# design.net
KiCad netlist of a schematic drawn in Altium Designer
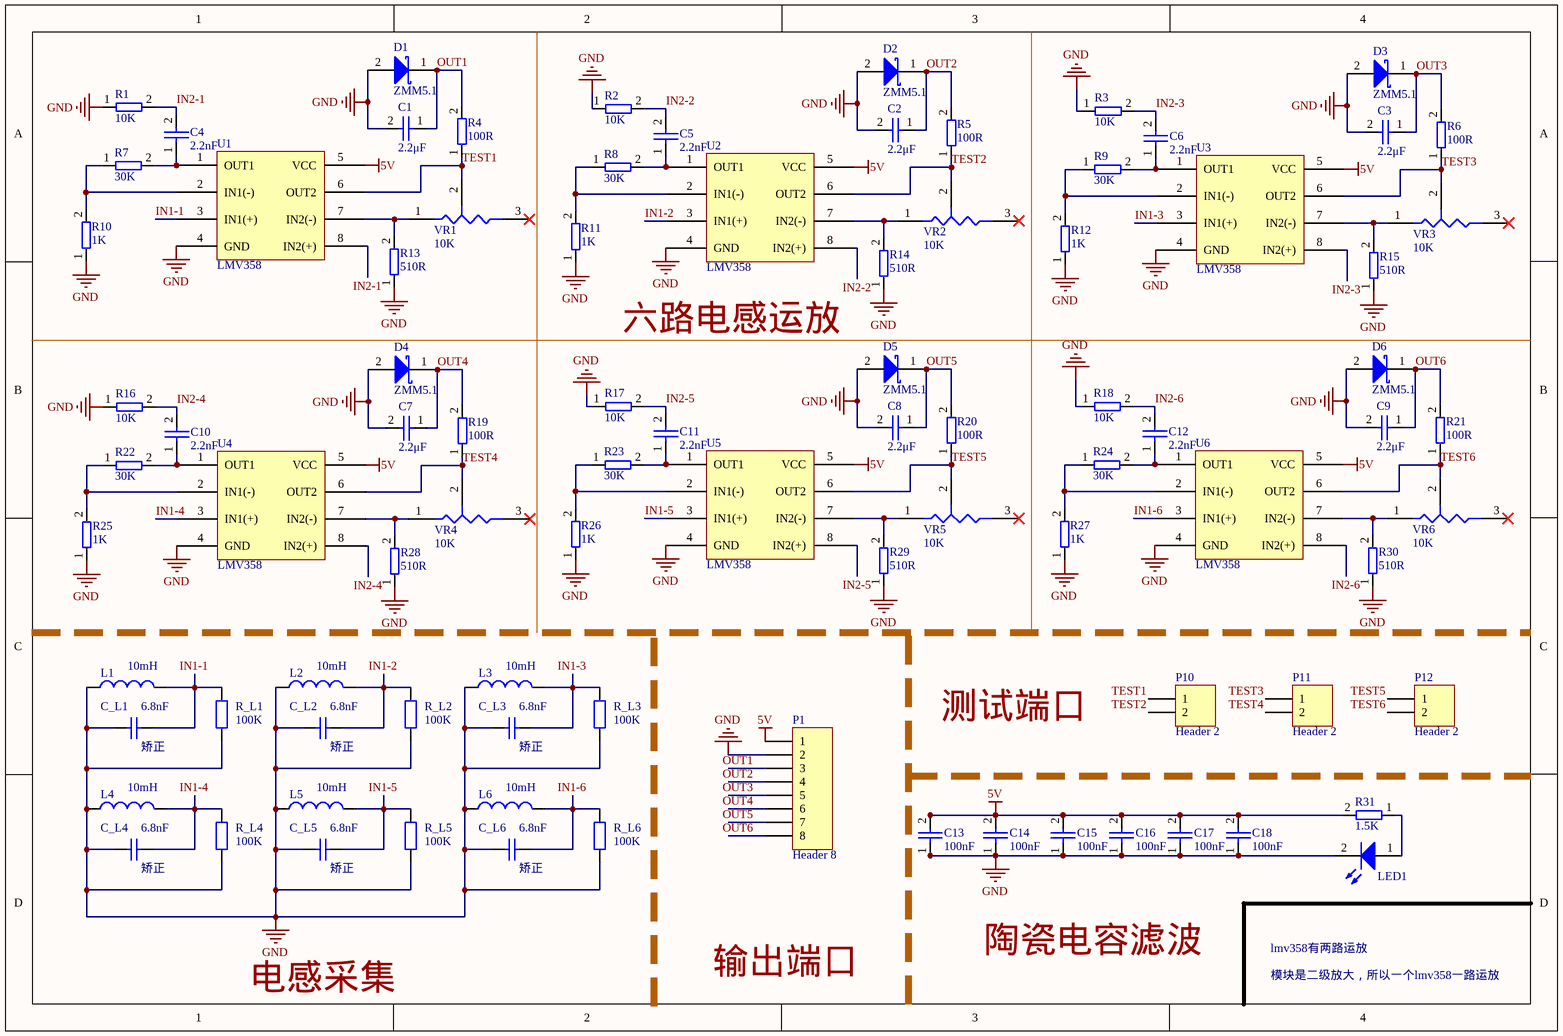
[diagram p0: 电感板原理图.SchDoc]

(export (version "E")
  (design (tool "Eeschema 10.0.6"))
  (components
    (comp (ref "C1") (value "2.2μF") (footprint "C 0603_L") (libsource (lib "燚龘") (part "Cap")))
    (comp (ref "C2") (value "2.2μF") (footprint "C 0603_L") (libsource (lib "燚龘") (part "Cap")))
    (comp (ref "C3") (value "2.2μF") (footprint "C 0603_L") (libsource (lib "燚龘") (part "Cap")))
    (comp (ref "C4") (value "2.2nF") (footprint "0805C") (libsource (lib "燚龘") (part "Cap")))
    (comp (ref "C5") (value "2.2nF") (footprint "0805C") (libsource (lib "燚龘") (part "Cap")))
    (comp (ref "C6") (value "2.2nF") (footprint "0805C") (libsource (lib "燚龘") (part "Cap")))
    (comp (ref "C7") (value "2.2μF") (footprint "C 0603_L") (libsource (lib "燚龘") (part "Cap")))
    (comp (ref "C8") (value "2.2μF") (footprint "C 0603_L") (libsource (lib "燚龘") (part "Cap")))
    (comp (ref "C9") (value "2.2μF") (footprint "C 0603_L") (libsource (lib "燚龘") (part "Cap")))
    (comp (ref "C10") (value "2.2nF") (footprint "0805C") (libsource (lib "燚龘") (part "Cap")))
    (comp (ref "C11") (value "2.2nF") (footprint "0805C") (libsource (lib "燚龘") (part "Cap")))
    (comp (ref "C12") (value "2.2nF") (footprint "0805C") (libsource (lib "燚龘") (part "Cap")))
    (comp (ref "C13")
      (value "100nF")
      (footprint "0805C")
      (description "陶瓷电容")
      (libsource (lib "燚龘") (part "Cap"))
    )
    (comp (ref "C14")
      (value "100nF")
      (footprint "0805C")
      (description "陶瓷电容")
      (libsource (lib "燚龘") (part "Cap"))
    )
    (comp (ref "C15")
      (value "100nF")
      (footprint "0805C")
      (description "陶瓷电容")
      (libsource (lib "燚龘") (part "Cap"))
    )
    (comp (ref "C16")
      (value "100nF")
      (footprint "0805C")
      (description "陶瓷电容")
      (libsource (lib "燚龘") (part "Cap"))
    )
    (comp (ref "C17")
      (value "100nF")
      (footprint "0805C")
      (description "陶瓷电容")
      (libsource (lib "燚龘") (part "Cap"))
    )
    (comp (ref "C18")
      (value "100nF")
      (footprint "0805C")
      (description "陶瓷电容")
      (libsource (lib "燚龘") (part "Cap"))
    )
    (comp (ref "C_L1")
      (value "矫正")
      (footprint "RAD-0.3")
      (description "Capacitor")
      (fields (field (name "ALTIUM_VALUE") "6.8nF") (field (name "PUBLISHER") "Altium Limited"))
      (libsource (lib "Miscellaneous Devices") (part "Cap"))
    )
    (comp (ref "C_L2")
      (value "矫正")
      (footprint "RAD-0.3")
      (description "Capacitor")
      (fields (field (name "ALTIUM_VALUE") "6.8nF") (field (name "PUBLISHER") "Altium Limited"))
      (libsource (lib "Miscellaneous Devices") (part "Cap"))
    )
    (comp (ref "C_L3")
      (value "矫正")
      (footprint "RAD-0.3")
      (description "Capacitor")
      (fields (field (name "ALTIUM_VALUE") "6.8nF") (field (name "PUBLISHER") "Altium Limited"))
      (libsource (lib "Miscellaneous Devices") (part "Cap"))
    )
    (comp (ref "C_L4")
      (value "矫正")
      (footprint "RAD-0.3")
      (description "Capacitor")
      (fields (field (name "ALTIUM_VALUE") "6.8nF") (field (name "PUBLISHER") "Altium Limited"))
      (libsource (lib "Miscellaneous Devices") (part "Cap"))
    )
    (comp (ref "C_L5")
      (value "矫正")
      (footprint "RAD-0.3")
      (description "Capacitor")
      (fields (field (name "ALTIUM_VALUE") "6.8nF") (field (name "PUBLISHER") "Altium Limited"))
      (libsource (lib "Miscellaneous Devices") (part "Cap"))
    )
    (comp (ref "C_L6")
      (value "矫正")
      (footprint "RAD-0.3")
      (description "Capacitor")
      (fields (field (name "ALTIUM_VALUE") "6.8nF") (field (name "PUBLISHER") "Altium Limited"))
      (libsource (lib "Miscellaneous Devices") (part "Cap"))
    )
    (comp (ref "D1")
      (value "ZMM5.1")
      (footprint "1206C")
      (description "Schottky Rectifier")
      (fields (field (name "PUBLISHER") "Altium Limited"))
      (libsource (lib "Miscellaneous Devices") (part "Diode 10TQ040"))
    )
    (comp (ref "D2")
      (value "ZMM5.1")
      (footprint "1206C")
      (description "Schottky Rectifier")
      (fields (field (name "PUBLISHER") "Altium Limited"))
      (libsource (lib "Miscellaneous Devices") (part "Diode 10TQ040"))
    )
    (comp (ref "D3")
      (value "ZMM5.1")
      (footprint "1206C")
      (description "Schottky Rectifier")
      (fields (field (name "PUBLISHER") "Altium Limited"))
      (libsource (lib "Miscellaneous Devices") (part "Diode 10TQ040"))
    )
    (comp (ref "D4")
      (value "ZMM5.1")
      (footprint "1206C")
      (description "Schottky Rectifier")
      (fields (field (name "PUBLISHER") "Altium Limited"))
      (libsource (lib "Miscellaneous Devices") (part "Diode 10TQ040"))
    )
    (comp (ref "D5")
      (value "ZMM5.1")
      (footprint "1206C")
      (description "Schottky Rectifier")
      (fields (field (name "PUBLISHER") "Altium Limited"))
      (libsource (lib "Miscellaneous Devices") (part "Diode 10TQ040"))
    )
    (comp (ref "D6")
      (value "ZMM5.1")
      (footprint "1206C")
      (description "Schottky Rectifier")
      (fields (field (name "PUBLISHER") "Altium Limited"))
      (libsource (lib "Miscellaneous Devices") (part "Diode 10TQ040"))
    )
    (comp (ref "L1")
      (value "10mH")
      (footprint "HDR1X2")
      (description "Inductor")
      (fields (field (name "PUBLISHER") "Altium Limited"))
      (libsource (lib "Miscellaneous Devices") (part "Inductor"))
    )
    (comp (ref "L2")
      (value "10mH")
      (footprint "HDR1X2")
      (description "Inductor")
      (fields (field (name "PUBLISHER") "Altium Limited"))
      (libsource (lib "Miscellaneous Devices") (part "Inductor"))
    )
    (comp (ref "L3")
      (value "10mH")
      (footprint "HDR1X2")
      (description "Inductor")
      (fields (field (name "PUBLISHER") "Altium Limited"))
      (libsource (lib "Miscellaneous Devices") (part "Inductor"))
    )
    (comp (ref "L4")
      (value "10mH")
      (footprint "HDR1X2")
      (description "Inductor")
      (fields (field (name "PUBLISHER") "Altium Limited"))
      (libsource (lib "Miscellaneous Devices") (part "Inductor"))
    )
    (comp (ref "L5")
      (value "10mH")
      (footprint "HDR1X2")
      (description "Inductor")
      (fields (field (name "PUBLISHER") "Altium Limited"))
      (libsource (lib "Miscellaneous Devices") (part "Inductor"))
    )
    (comp (ref "L6")
      (value "10mH")
      (footprint "HDR1X2")
      (description "Inductor")
      (fields (field (name "PUBLISHER") "Altium Limited"))
      (libsource (lib "Miscellaneous Devices") (part "Inductor"))
    )
    (comp (ref "LED1")
      (value "LED")
      (footprint "LED0805R")
      (description "Typical BLUE SiC LED")
      (fields (field (name "PUBLISHER") "Altium Limited"))
      (libsource (lib "智能车修改版") (part "LED3"))
    )
    (comp (ref "P1")
      (value "Header 8")
      (footprint "HDR1X8")
      (description "Header, 8-Pin")
      (fields (field (name "PUBLISHER") "Altium Limited"))
      (libsource (lib "红旗_SchLib_V1.0") (part "Header 8"))
    )
    (comp (ref "P10")
      (value "Header 2")
      (footprint "HDR1X2")
      (description "Header, 2-Pin")
      (fields (field (name "PUBLISHER") "Altium Limited"))
      (libsource (lib "Miscellaneous Connectors") (part "Header 2"))
    )
    (comp (ref "P11")
      (value "Header 2")
      (footprint "HDR1X2")
      (description "Header, 2-Pin")
      (fields (field (name "PUBLISHER") "Altium Limited"))
      (libsource (lib "Miscellaneous Connectors") (part "Header 2"))
    )
    (comp (ref "P12")
      (value "Header 2")
      (footprint "HDR1X2")
      (description "Header, 2-Pin")
      (fields (field (name "PUBLISHER") "Altium Limited"))
      (libsource (lib "Miscellaneous Connectors") (part "Header 2"))
    )
    (comp (ref "R1") (value "10K") (footprint "0805-1R") (libsource (lib "燚龘主控") (part "0805R")))
    (comp (ref "R2") (value "10K") (footprint "0805-1R") (libsource (lib "燚龘主控") (part "0805R")))
    (comp (ref "R3") (value "10K") (footprint "0805-1R") (libsource (lib "燚龘主控") (part "0805R")))
    (comp (ref "R4") (value "100R") (footprint "0805-0R") (libsource (lib "燚龘主控") (part "0805R")))
    (comp (ref "R5") (value "100R") (footprint "0805-0R") (libsource (lib "燚龘主控") (part "0805R")))
    (comp (ref "R6") (value "100R") (footprint "0805-0R") (libsource (lib "燚龘主控") (part "0805R")))
    (comp (ref "R7") (value "30K") (footprint "0805-1R") (libsource (lib "燚龘主控") (part "0805R")))
    (comp (ref "R8") (value "30K") (footprint "0805-1R") (libsource (lib "燚龘主控") (part "0805R")))
    (comp (ref "R9") (value "30K") (footprint "0805-1R") (libsource (lib "燚龘主控") (part "0805R")))
    (comp (ref "R10") (value "1K") (footprint "0805-1R") (libsource (lib "燚龘主控") (part "0805R")))
    (comp (ref "R11") (value "1K") (footprint "0805-1R") (libsource (lib "燚龘主控") (part "0805R")))
    (comp (ref "R12") (value "1K") (footprint "0805-1R") (libsource (lib "燚龘主控") (part "0805R")))
    (comp (ref "R13") (value "510R") (footprint "0805-0R") (libsource (lib "燚龘主控") (part "0805R")))
    (comp (ref "R14") (value "510R") (footprint "0805-0R") (libsource (lib "燚龘主控") (part "0805R")))
    (comp (ref "R15") (value "510R") (footprint "0805-0R") (libsource (lib "燚龘主控") (part "0805R")))
    (comp (ref "R16") (value "10K") (footprint "0805-1R") (libsource (lib "燚龘主控") (part "0805R")))
    (comp (ref "R17") (value "10K") (footprint "0805-1R") (libsource (lib "燚龘主控") (part "0805R")))
    (comp (ref "R18") (value "10K") (footprint "0805-1R") (libsource (lib "燚龘主控") (part "0805R")))
    (comp (ref "R19") (value "100R") (footprint "0805-0R") (libsource (lib "燚龘主控") (part "0805R")))
    (comp (ref "R20") (value "100R") (footprint "0805-0R") (libsource (lib "燚龘主控") (part "0805R")))
    (comp (ref "R21") (value "100R") (footprint "0805-0R") (libsource (lib "燚龘主控") (part "0805R")))
    (comp (ref "R22") (value "30K") (footprint "0805-1R") (libsource (lib "燚龘主控") (part "0805R")))
    (comp (ref "R23") (value "30K") (footprint "0805-1R") (libsource (lib "燚龘主控") (part "0805R")))
    (comp (ref "R24") (value "30K") (footprint "0805-1R") (libsource (lib "燚龘主控") (part "0805R")))
    (comp (ref "R25") (value "1K") (footprint "0805-1R") (libsource (lib "燚龘主控") (part "0805R")))
    (comp (ref "R26") (value "1K") (footprint "0805-1R") (libsource (lib "燚龘主控") (part "0805R")))
    (comp (ref "R27") (value "1K") (footprint "0805-1R") (libsource (lib "燚龘主控") (part "0805R")))
    (comp (ref "R28") (value "510R") (footprint "0805-0R") (libsource (lib "燚龘主控") (part "0805R")))
    (comp (ref "R29") (value "510R") (footprint "0805-0R") (libsource (lib "燚龘主控") (part "0805R")))
    (comp (ref "R30") (value "510R") (footprint "0805-0R") (libsource (lib "燚龘主控") (part "0805R")))
    (comp (ref "R31") (value "1.5K") (footprint "0805-1R") (libsource (lib "燚龘主控") (part "0805R")))
    (comp (ref "R_L1")
      (value "100K")
      (footprint "0805-1R")
      (description "Resistor")
      (fields (field (name "Comment") "Res2") (field (name "PUBLISHER") "Altium Limited"))
      (libsource (lib "Miscellaneous Devices") (part "Res2"))
    )
    (comp (ref "R_L2")
      (value "100K")
      (footprint "0805-1R")
      (description "Resistor")
      (fields (field (name "Comment") "Res2") (field (name "PUBLISHER") "Altium Limited"))
      (libsource (lib "Miscellaneous Devices") (part "Res2"))
    )
    (comp (ref "R_L3")
      (value "100K")
      (footprint "0805-1R")
      (description "Resistor")
      (fields (field (name "Comment") "Res2") (field (name "PUBLISHER") "Altium Limited"))
      (libsource (lib "Miscellaneous Devices") (part "Res2"))
    )
    (comp (ref "R_L4")
      (value "100K")
      (footprint "0805-1R")
      (description "Resistor")
      (fields (field (name "Comment") "Res2") (field (name "PUBLISHER") "Altium Limited"))
      (libsource (lib "Miscellaneous Devices") (part "Res2"))
    )
    (comp (ref "R_L5")
      (value "100K")
      (footprint "0805-1R")
      (description "Resistor")
      (fields (field (name "Comment") "Res2") (field (name "PUBLISHER") "Altium Limited"))
      (libsource (lib "Miscellaneous Devices") (part "Res2"))
    )
    (comp (ref "R_L6")
      (value "100K")
      (footprint "0805-1R")
      (description "Resistor")
      (fields (field (name "Comment") "Res2") (field (name "PUBLISHER") "Altium Limited"))
      (libsource (lib "Miscellaneous Devices") (part "Res2"))
    )
    (comp (ref "U1") (value "LMV358") (footprint "SOP8") (libsource (lib "Schlib1") (part "LMV358")))
    (comp (ref "U2") (value "LMV358") (footprint "SOP8") (libsource (lib "Schlib1") (part "LMV358")))
    (comp (ref "U3") (value "LMV358") (footprint "SOP8") (libsource (lib "Schlib1") (part "LMV358")))
    (comp (ref "U4") (value "LMV358") (footprint "SOP8") (libsource (lib "Schlib1") (part "LMV358")))
    (comp (ref "U5") (value "LMV358") (footprint "SOP8") (libsource (lib "Schlib1") (part "LMV358")))
    (comp (ref "U6") (value "LMV358") (footprint "SOP8") (libsource (lib "Schlib1") (part "LMV358")))
    (comp (ref "VR1")
      (value "10K")
      (footprint "3296W")
      (description "Tapped Resistor")
      (fields (field (name "PUBLISHER") "Altium Limited"))
      (libsource (lib "Miscellaneous Devices") (part "Res Tap"))
    )
    (comp (ref "VR2")
      (value "10K")
      (footprint "3296W")
      (description "Tapped Resistor")
      (fields (field (name "PUBLISHER") "Altium Limited"))
      (libsource (lib "Miscellaneous Devices") (part "Res Tap"))
    )
    (comp (ref "VR3")
      (value "10K")
      (footprint "3296W")
      (description "Tapped Resistor")
      (fields (field (name "PUBLISHER") "Altium Limited"))
      (libsource (lib "Miscellaneous Devices") (part "Res Tap"))
    )
    (comp (ref "VR4")
      (value "10K")
      (footprint "3296W")
      (description "Tapped Resistor")
      (fields (field (name "PUBLISHER") "Altium Limited"))
      (libsource (lib "Miscellaneous Devices") (part "Res Tap"))
    )
    (comp (ref "VR5")
      (value "10K")
      (footprint "3296W")
      (description "Tapped Resistor")
      (fields (field (name "PUBLISHER") "Altium Limited"))
      (libsource (lib "Miscellaneous Devices") (part "Res Tap"))
    )
    (comp (ref "VR6")
      (value "10K")
      (footprint "3296W")
      (description "Tapped Resistor")
      (fields (field (name "PUBLISHER") "Altium Limited"))
      (libsource (lib "Miscellaneous Devices") (part "Res Tap"))
    )
  )
  (nets
    (net (code "1") (name "/IN1-1") (class "Default")
      (node (ref "C_L1") (pin "2") (pinfunction "2_2") (pintype "passive"))
      (node (ref "L1") (pin "2") (pinfunction "2_2") (pintype "passive"))
      (node (ref "R_L1") (pin "2") (pinfunction "2_2") (pintype "passive"))
      (node (ref "U1") (pin "3") (pinfunction "IN1(+)_3") (pintype "passive"))
    )
    (net (code "2") (name "/IN1-2") (class "Default")
      (node (ref "C_L2") (pin "2") (pinfunction "2_2") (pintype "passive"))
      (node (ref "L2") (pin "2") (pinfunction "2_2") (pintype "passive"))
      (node (ref "R_L2") (pin "2") (pinfunction "2_2") (pintype "passive"))
      (node (ref "U2") (pin "3") (pinfunction "IN1(+)_3") (pintype "passive"))
    )
    (net (code "3") (name "/IN1-3") (class "Default")
      (node (ref "C_L3") (pin "2") (pinfunction "2_2") (pintype "passive"))
      (node (ref "L3") (pin "2") (pinfunction "2_2") (pintype "passive"))
      (node (ref "R_L3") (pin "2") (pinfunction "2_2") (pintype "passive"))
      (node (ref "U3") (pin "3") (pinfunction "IN1(+)_3") (pintype "passive"))
    )
    (net (code "4") (name "/IN1-4") (class "Default")
      (node (ref "C_L4") (pin "2") (pinfunction "2_2") (pintype "passive"))
      (node (ref "L4") (pin "2") (pinfunction "2_2") (pintype "passive"))
      (node (ref "R_L4") (pin "2") (pinfunction "2_2") (pintype "passive"))
      (node (ref "U4") (pin "3") (pinfunction "IN1(+)_3") (pintype "passive"))
    )
    (net (code "5") (name "/IN1-5") (class "Default")
      (node (ref "C_L5") (pin "2") (pinfunction "2_2") (pintype "passive"))
      (node (ref "L5") (pin "2") (pinfunction "2_2") (pintype "passive"))
      (node (ref "R_L5") (pin "2") (pinfunction "2_2") (pintype "passive"))
      (node (ref "U5") (pin "3") (pinfunction "IN1(+)_3") (pintype "passive"))
    )
    (net (code "6") (name "/IN1-6") (class "Default")
      (node (ref "C_L6") (pin "2") (pinfunction "2_2") (pintype "passive"))
      (node (ref "L6") (pin "2") (pinfunction "2_2") (pintype "passive"))
      (node (ref "R_L6") (pin "2") (pinfunction "2_2") (pintype "passive"))
      (node (ref "U6") (pin "3") (pinfunction "IN1(+)_3") (pintype "passive"))
    )
    (net (code "7") (name "/IN2-1") (class "Default")
      (node (ref "C4") (pin "2") (pinfunction "2_2") (pintype "passive"))
      (node (ref "R1") (pin "2") (pinfunction "2_2") (pintype "passive"))
      (node (ref "U1") (pin "8") (pinfunction "IN2(+)_8") (pintype "passive"))
    )
    (net (code "8") (name "/IN2-2") (class "Default")
      (node (ref "C5") (pin "2") (pinfunction "2_2") (pintype "passive"))
      (node (ref "R2") (pin "2") (pinfunction "2_2") (pintype "passive"))
      (node (ref "U2") (pin "8") (pinfunction "IN2(+)_8") (pintype "passive"))
    )
    (net (code "9") (name "/IN2-3") (class "Default")
      (node (ref "C6") (pin "2") (pinfunction "2_2") (pintype "passive"))
      (node (ref "R3") (pin "2") (pinfunction "2_2") (pintype "passive"))
      (node (ref "U3") (pin "8") (pinfunction "IN2(+)_8") (pintype "passive"))
    )
    (net (code "10") (name "/IN2-4") (class "Default")
      (node (ref "C10") (pin "2") (pinfunction "2_2") (pintype "passive"))
      (node (ref "R16") (pin "2") (pinfunction "2_2") (pintype "passive"))
      (node (ref "U4") (pin "8") (pinfunction "IN2(+)_8") (pintype "passive"))
    )
    (net (code "11") (name "/IN2-5") (class "Default")
      (node (ref "C11") (pin "2") (pinfunction "2_2") (pintype "passive"))
      (node (ref "R17") (pin "2") (pinfunction "2_2") (pintype "passive"))
      (node (ref "U5") (pin "8") (pinfunction "IN2(+)_8") (pintype "passive"))
    )
    (net (code "12") (name "/IN2-6") (class "Default")
      (node (ref "C12") (pin "2") (pinfunction "2_2") (pintype "passive"))
      (node (ref "R18") (pin "2") (pinfunction "2_2") (pintype "passive"))
      (node (ref "U6") (pin "8") (pinfunction "IN2(+)_8") (pintype "passive"))
    )
    (net (code "13") (name "/OUT1") (class "Default")
      (node (ref "C1") (pin "1") (pinfunction "1_1") (pintype "passive"))
      (node (ref "D1") (pin "1") (pinfunction "K_1") (pintype "passive"))
      (node (ref "P1") (pin "3") (pinfunction "3_3") (pintype "passive"))
      (node (ref "R4") (pin "2") (pinfunction "2_2") (pintype "passive"))
    )
    (net (code "14") (name "/OUT2") (class "Default")
      (node (ref "C2") (pin "1") (pinfunction "1_1") (pintype "passive"))
      (node (ref "D2") (pin "1") (pinfunction "K_1") (pintype "passive"))
      (node (ref "P1") (pin "4") (pinfunction "4_4") (pintype "passive"))
      (node (ref "R5") (pin "2") (pinfunction "2_2") (pintype "passive"))
    )
    (net (code "15") (name "/OUT3") (class "Default")
      (node (ref "C3") (pin "1") (pinfunction "1_1") (pintype "passive"))
      (node (ref "D3") (pin "1") (pinfunction "K_1") (pintype "passive"))
      (node (ref "P1") (pin "5") (pinfunction "5_5") (pintype "passive"))
      (node (ref "R6") (pin "2") (pinfunction "2_2") (pintype "passive"))
    )
    (net (code "16") (name "/OUT4") (class "Default")
      (node (ref "C7") (pin "1") (pinfunction "1_1") (pintype "passive"))
      (node (ref "D4") (pin "1") (pinfunction "K_1") (pintype "passive"))
      (node (ref "P1") (pin "6") (pinfunction "6_6") (pintype "passive"))
      (node (ref "R19") (pin "2") (pinfunction "2_2") (pintype "passive"))
    )
    (net (code "17") (name "/OUT5") (class "Default")
      (node (ref "C8") (pin "1") (pinfunction "1_1") (pintype "passive"))
      (node (ref "D5") (pin "1") (pinfunction "K_1") (pintype "passive"))
      (node (ref "P1") (pin "7") (pinfunction "7_7") (pintype "passive"))
      (node (ref "R20") (pin "2") (pinfunction "2_2") (pintype "passive"))
    )
    (net (code "18") (name "/OUT6") (class "Default")
      (node (ref "C9") (pin "1") (pinfunction "1_1") (pintype "passive"))
      (node (ref "D6") (pin "1") (pinfunction "K_1") (pintype "passive"))
      (node (ref "P1") (pin "8") (pinfunction "8_8") (pintype "passive"))
      (node (ref "R21") (pin "2") (pinfunction "2_2") (pintype "passive"))
    )
    (net (code "19") (name "/TEST1") (class "Default")
      (node (ref "P10") (pin "1") (pinfunction "1_1") (pintype "passive"))
      (node (ref "R4") (pin "1") (pinfunction "1_1") (pintype "passive"))
      (node (ref "U1") (pin "6") (pinfunction "OUT2_6") (pintype "passive"))
      (node (ref "VR1") (pin "2") (pinfunction "TAP_2") (pintype "passive"))
    )
    (net (code "20") (name "/TEST2") (class "Default")
      (node (ref "P10") (pin "2") (pinfunction "2_2") (pintype "passive"))
      (node (ref "R5") (pin "1") (pinfunction "1_1") (pintype "passive"))
      (node (ref "U2") (pin "6") (pinfunction "OUT2_6") (pintype "passive"))
      (node (ref "VR2") (pin "2") (pinfunction "TAP_2") (pintype "passive"))
    )
    (net (code "21") (name "/TEST3") (class "Default")
      (node (ref "P11") (pin "1") (pinfunction "1_1") (pintype "passive"))
      (node (ref "R6") (pin "1") (pinfunction "1_1") (pintype "passive"))
      (node (ref "U3") (pin "6") (pinfunction "OUT2_6") (pintype "passive"))
      (node (ref "VR3") (pin "2") (pinfunction "TAP_2") (pintype "passive"))
    )
    (net (code "22") (name "/TEST4") (class "Default")
      (node (ref "P11") (pin "2") (pinfunction "2_2") (pintype "passive"))
      (node (ref "R19") (pin "1") (pinfunction "1_1") (pintype "passive"))
      (node (ref "U4") (pin "6") (pinfunction "OUT2_6") (pintype "passive"))
      (node (ref "VR4") (pin "2") (pinfunction "TAP_2") (pintype "passive"))
    )
    (net (code "23") (name "/TEST5") (class "Default")
      (node (ref "P12") (pin "1") (pinfunction "1_1") (pintype "passive"))
      (node (ref "R20") (pin "1") (pinfunction "1_1") (pintype "passive"))
      (node (ref "U5") (pin "6") (pinfunction "OUT2_6") (pintype "passive"))
      (node (ref "VR5") (pin "2") (pinfunction "TAP_2") (pintype "passive"))
    )
    (net (code "24") (name "/TEST6") (class "Default")
      (node (ref "P12") (pin "2") (pinfunction "2_2") (pintype "passive"))
      (node (ref "R21") (pin "1") (pinfunction "1_1") (pintype "passive"))
      (node (ref "U6") (pin "6") (pinfunction "OUT2_6") (pintype "passive"))
      (node (ref "VR6") (pin "2") (pinfunction "TAP_2") (pintype "passive"))
    )
    (net (code "25") (name "5V") (class "Default")
      (node (ref "C13") (pin "2") (pinfunction "2_2") (pintype "passive"))
      (node (ref "C14") (pin "2") (pinfunction "2_2") (pintype "passive"))
      (node (ref "C15") (pin "2") (pinfunction "2_2") (pintype "passive"))
      (node (ref "C16") (pin "2") (pinfunction "2_2") (pintype "passive"))
      (node (ref "C17") (pin "2") (pinfunction "2_2") (pintype "passive"))
      (node (ref "C18") (pin "2") (pinfunction "2_2") (pintype "passive"))
      (node (ref "P1") (pin "1") (pinfunction "1_1") (pintype "passive"))
      (node (ref "R31") (pin "2") (pinfunction "2_2") (pintype "passive"))
      (node (ref "U1") (pin "5") (pinfunction "VCC_5") (pintype "passive"))
      (node (ref "U2") (pin "5") (pinfunction "VCC_5") (pintype "passive"))
      (node (ref "U3") (pin "5") (pinfunction "VCC_5") (pintype "passive"))
      (node (ref "U4") (pin "5") (pinfunction "VCC_5") (pintype "passive"))
      (node (ref "U5") (pin "5") (pinfunction "VCC_5") (pintype "passive"))
      (node (ref "U6") (pin "5") (pinfunction "VCC_5") (pintype "passive"))
    )
    (net (code "26") (name "GND") (class "Default")
      (node (ref "C1") (pin "2") (pinfunction "2_2") (pintype "passive"))
      (node (ref "C13") (pin "1") (pinfunction "1_1") (pintype "passive"))
      (node (ref "C14") (pin "1") (pinfunction "1_1") (pintype "passive"))
      (node (ref "C15") (pin "1") (pinfunction "1_1") (pintype "passive"))
      (node (ref "C16") (pin "1") (pinfunction "1_1") (pintype "passive"))
      (node (ref "C17") (pin "1") (pinfunction "1_1") (pintype "passive"))
      (node (ref "C18") (pin "1") (pinfunction "1_1") (pintype "passive"))
      (node (ref "C2") (pin "2") (pinfunction "2_2") (pintype "passive"))
      (node (ref "C3") (pin "2") (pinfunction "2_2") (pintype "passive"))
      (node (ref "C7") (pin "2") (pinfunction "2_2") (pintype "passive"))
      (node (ref "C8") (pin "2") (pinfunction "2_2") (pintype "passive"))
      (node (ref "C9") (pin "2") (pinfunction "2_2") (pintype "passive"))
      (node (ref "C_L1") (pin "1") (pinfunction "1_1") (pintype "passive"))
      (node (ref "C_L2") (pin "1") (pinfunction "1_1") (pintype "passive"))
      (node (ref "C_L3") (pin "1") (pinfunction "1_1") (pintype "passive"))
      (node (ref "C_L4") (pin "1") (pinfunction "1_1") (pintype "passive"))
      (node (ref "C_L5") (pin "1") (pinfunction "1_1") (pintype "passive"))
      (node (ref "C_L6") (pin "1") (pinfunction "1_1") (pintype "passive"))
      (node (ref "D1") (pin "2") (pinfunction "A_2") (pintype "passive"))
      (node (ref "D2") (pin "2") (pinfunction "A_2") (pintype "passive"))
      (node (ref "D3") (pin "2") (pinfunction "A_2") (pintype "passive"))
      (node (ref "D4") (pin "2") (pinfunction "A_2") (pintype "passive"))
      (node (ref "D5") (pin "2") (pinfunction "A_2") (pintype "passive"))
      (node (ref "D6") (pin "2") (pinfunction "A_2") (pintype "passive"))
      (node (ref "L1") (pin "1") (pinfunction "1_1") (pintype "passive"))
      (node (ref "L2") (pin "1") (pinfunction "1_1") (pintype "passive"))
      (node (ref "L3") (pin "1") (pinfunction "1_1") (pintype "passive"))
      (node (ref "L4") (pin "1") (pinfunction "1_1") (pintype "passive"))
      (node (ref "L5") (pin "1") (pinfunction "1_1") (pintype "passive"))
      (node (ref "L6") (pin "1") (pinfunction "1_1") (pintype "passive"))
      (node (ref "LED1") (pin "2") (pinfunction "K_2") (pintype "passive"))
      (node (ref "P1") (pin "2") (pinfunction "2_2") (pintype "passive"))
      (node (ref "R1") (pin "1") (pinfunction "1_1") (pintype "passive"))
      (node (ref "R10") (pin "1") (pinfunction "1_1") (pintype "passive"))
      (node (ref "R11") (pin "1") (pinfunction "1_1") (pintype "passive"))
      (node (ref "R12") (pin "1") (pinfunction "1_1") (pintype "passive"))
      (node (ref "R13") (pin "1") (pinfunction "1_1") (pintype "passive"))
      (node (ref "R14") (pin "1") (pinfunction "1_1") (pintype "passive"))
      (node (ref "R15") (pin "1") (pinfunction "1_1") (pintype "passive"))
      (node (ref "R16") (pin "1") (pinfunction "1_1") (pintype "passive"))
      (node (ref "R17") (pin "1") (pinfunction "1_1") (pintype "passive"))
      (node (ref "R18") (pin "1") (pinfunction "1_1") (pintype "passive"))
      (node (ref "R2") (pin "1") (pinfunction "1_1") (pintype "passive"))
      (node (ref "R25") (pin "1") (pinfunction "1_1") (pintype "passive"))
      (node (ref "R26") (pin "1") (pinfunction "1_1") (pintype "passive"))
      (node (ref "R27") (pin "1") (pinfunction "1_1") (pintype "passive"))
      (node (ref "R28") (pin "1") (pinfunction "1_1") (pintype "passive"))
      (node (ref "R29") (pin "1") (pinfunction "1_1") (pintype "passive"))
      (node (ref "R3") (pin "1") (pinfunction "1_1") (pintype "passive"))
      (node (ref "R30") (pin "1") (pinfunction "1_1") (pintype "passive"))
      (node (ref "R_L1") (pin "1") (pinfunction "1_1") (pintype "passive"))
      (node (ref "R_L2") (pin "1") (pinfunction "1_1") (pintype "passive"))
      (node (ref "R_L3") (pin "1") (pinfunction "1_1") (pintype "passive"))
      (node (ref "R_L4") (pin "1") (pinfunction "1_1") (pintype "passive"))
      (node (ref "R_L5") (pin "1") (pinfunction "1_1") (pintype "passive"))
      (node (ref "R_L6") (pin "1") (pinfunction "1_1") (pintype "passive"))
      (node (ref "U1") (pin "4") (pinfunction "GND_4") (pintype "passive"))
      (node (ref "U2") (pin "4") (pinfunction "GND_4") (pintype "passive"))
      (node (ref "U3") (pin "4") (pinfunction "GND_4") (pintype "passive"))
      (node (ref "U4") (pin "4") (pinfunction "GND_4") (pintype "passive"))
      (node (ref "U5") (pin "4") (pinfunction "GND_4") (pintype "passive"))
      (node (ref "U6") (pin "4") (pinfunction "GND_4") (pintype "passive"))
    )
    (net (code "27") (name "Net-(LED1-A)") (class "Default")
      (node (ref "LED1") (pin "1") (pinfunction "A_1") (pintype "passive"))
      (node (ref "R31") (pin "1") (pinfunction "1_1") (pintype "passive"))
    )
    (net (code "28") (name "Net-(U1-IN1(-))") (class "Default")
      (node (ref "R10") (pin "2") (pinfunction "2_2") (pintype "passive"))
      (node (ref "R7") (pin "1") (pinfunction "1_1") (pintype "passive"))
      (node (ref "U1") (pin "2") (pinfunction "IN1(-)_2") (pintype "passive"))
    )
    (net (code "29") (name "Net-(U1-IN2(-))") (class "Default")
      (node (ref "R13") (pin "2") (pinfunction "2_2") (pintype "passive"))
      (node (ref "U1") (pin "7") (pinfunction "IN2(-)_7") (pintype "passive"))
      (node (ref "VR1") (pin "1") (pinfunction "A_1") (pintype "passive"))
    )
    (net (code "30") (name "Net-(U1-OUT1)") (class "Default")
      (node (ref "C4") (pin "1") (pinfunction "1_1") (pintype "passive"))
      (node (ref "R7") (pin "2") (pinfunction "2_2") (pintype "passive"))
      (node (ref "U1") (pin "1") (pinfunction "OUT1_1") (pintype "passive"))
    )
    (net (code "31") (name "Net-(U2-IN1(-))") (class "Default")
      (node (ref "R11") (pin "2") (pinfunction "2_2") (pintype "passive"))
      (node (ref "R8") (pin "1") (pinfunction "1_1") (pintype "passive"))
      (node (ref "U2") (pin "2") (pinfunction "IN1(-)_2") (pintype "passive"))
    )
    (net (code "32") (name "Net-(U2-IN2(-))") (class "Default")
      (node (ref "R14") (pin "2") (pinfunction "2_2") (pintype "passive"))
      (node (ref "U2") (pin "7") (pinfunction "IN2(-)_7") (pintype "passive"))
      (node (ref "VR2") (pin "1") (pinfunction "A_1") (pintype "passive"))
    )
    (net (code "33") (name "Net-(U2-OUT1)") (class "Default")
      (node (ref "C5") (pin "1") (pinfunction "1_1") (pintype "passive"))
      (node (ref "R8") (pin "2") (pinfunction "2_2") (pintype "passive"))
      (node (ref "U2") (pin "1") (pinfunction "OUT1_1") (pintype "passive"))
    )
    (net (code "34") (name "Net-(U3-IN1(-))") (class "Default")
      (node (ref "R12") (pin "2") (pinfunction "2_2") (pintype "passive"))
      (node (ref "R9") (pin "1") (pinfunction "1_1") (pintype "passive"))
      (node (ref "U3") (pin "2") (pinfunction "IN1(-)_2") (pintype "passive"))
    )
    (net (code "35") (name "Net-(U3-IN2(-))") (class "Default")
      (node (ref "R15") (pin "2") (pinfunction "2_2") (pintype "passive"))
      (node (ref "U3") (pin "7") (pinfunction "IN2(-)_7") (pintype "passive"))
      (node (ref "VR3") (pin "1") (pinfunction "A_1") (pintype "passive"))
    )
    (net (code "36") (name "Net-(U3-OUT1)") (class "Default")
      (node (ref "C6") (pin "1") (pinfunction "1_1") (pintype "passive"))
      (node (ref "R9") (pin "2") (pinfunction "2_2") (pintype "passive"))
      (node (ref "U3") (pin "1") (pinfunction "OUT1_1") (pintype "passive"))
    )
    (net (code "37") (name "Net-(U4-IN1(-))") (class "Default")
      (node (ref "R22") (pin "1") (pinfunction "1_1") (pintype "passive"))
      (node (ref "R25") (pin "2") (pinfunction "2_2") (pintype "passive"))
      (node (ref "U4") (pin "2") (pinfunction "IN1(-)_2") (pintype "passive"))
    )
    (net (code "38") (name "Net-(U4-IN2(-))") (class "Default")
      (node (ref "R28") (pin "2") (pinfunction "2_2") (pintype "passive"))
      (node (ref "U4") (pin "7") (pinfunction "IN2(-)_7") (pintype "passive"))
      (node (ref "VR4") (pin "1") (pinfunction "A_1") (pintype "passive"))
    )
    (net (code "39") (name "Net-(U4-OUT1)") (class "Default")
      (node (ref "C10") (pin "1") (pinfunction "1_1") (pintype "passive"))
      (node (ref "R22") (pin "2") (pinfunction "2_2") (pintype "passive"))
      (node (ref "U4") (pin "1") (pinfunction "OUT1_1") (pintype "passive"))
    )
    (net (code "40") (name "Net-(U5-IN1(-))") (class "Default")
      (node (ref "R23") (pin "1") (pinfunction "1_1") (pintype "passive"))
      (node (ref "R26") (pin "2") (pinfunction "2_2") (pintype "passive"))
      (node (ref "U5") (pin "2") (pinfunction "IN1(-)_2") (pintype "passive"))
    )
    (net (code "41") (name "Net-(U5-IN2(-))") (class "Default")
      (node (ref "R29") (pin "2") (pinfunction "2_2") (pintype "passive"))
      (node (ref "U5") (pin "7") (pinfunction "IN2(-)_7") (pintype "passive"))
      (node (ref "VR5") (pin "1") (pinfunction "A_1") (pintype "passive"))
    )
    (net (code "42") (name "Net-(U5-OUT1)") (class "Default")
      (node (ref "C11") (pin "1") (pinfunction "1_1") (pintype "passive"))
      (node (ref "R23") (pin "2") (pinfunction "2_2") (pintype "passive"))
      (node (ref "U5") (pin "1") (pinfunction "OUT1_1") (pintype "passive"))
    )
    (net (code "43") (name "Net-(U6-IN1(-))") (class "Default")
      (node (ref "R24") (pin "1") (pinfunction "1_1") (pintype "passive"))
      (node (ref "R27") (pin "2") (pinfunction "2_2") (pintype "passive"))
      (node (ref "U6") (pin "2") (pinfunction "IN1(-)_2") (pintype "passive"))
    )
    (net (code "44") (name "Net-(U6-IN2(-))") (class "Default")
      (node (ref "R30") (pin "2") (pinfunction "2_2") (pintype "passive"))
      (node (ref "U6") (pin "7") (pinfunction "IN2(-)_7") (pintype "passive"))
      (node (ref "VR6") (pin "1") (pinfunction "A_1") (pintype "passive"))
    )
    (net (code "45") (name "Net-(U6-OUT1)") (class "Default")
      (node (ref "C12") (pin "1") (pinfunction "1_1") (pintype "passive"))
      (node (ref "R24") (pin "2") (pinfunction "2_2") (pintype "passive"))
      (node (ref "U6") (pin "1") (pinfunction "OUT1_1") (pintype "passive"))
    )
    (net (code "46") (name "unconnected-(VR1-B-Pad3)") (class "Default")
      (node (ref "VR1") (pin "3") (pinfunction "B_3") (pintype "passive+no_connect"))
    )
    (net (code "47") (name "unconnected-(VR2-B-Pad3)") (class "Default")
      (node (ref "VR2") (pin "3") (pinfunction "B_3") (pintype "passive+no_connect"))
    )
    (net (code "48") (name "unconnected-(VR3-B-Pad3)") (class "Default")
      (node (ref "VR3") (pin "3") (pinfunction "B_3") (pintype "passive+no_connect"))
    )
    (net (code "49") (name "unconnected-(VR4-B-Pad3)") (class "Default")
      (node (ref "VR4") (pin "3") (pinfunction "B_3") (pintype "passive+no_connect"))
    )
    (net (code "50") (name "unconnected-(VR5-B-Pad3)") (class "Default")
      (node (ref "VR5") (pin "3") (pinfunction "B_3") (pintype "passive+no_connect"))
    )
    (net (code "51") (name "unconnected-(VR6-B-Pad3)") (class "Default")
      (node (ref "VR6") (pin "3") (pinfunction "B_3") (pintype "passive+no_connect"))
    )
  )
)
